# BinaryClock.net
KiCad netlist of a schematic drawn in EAGLE
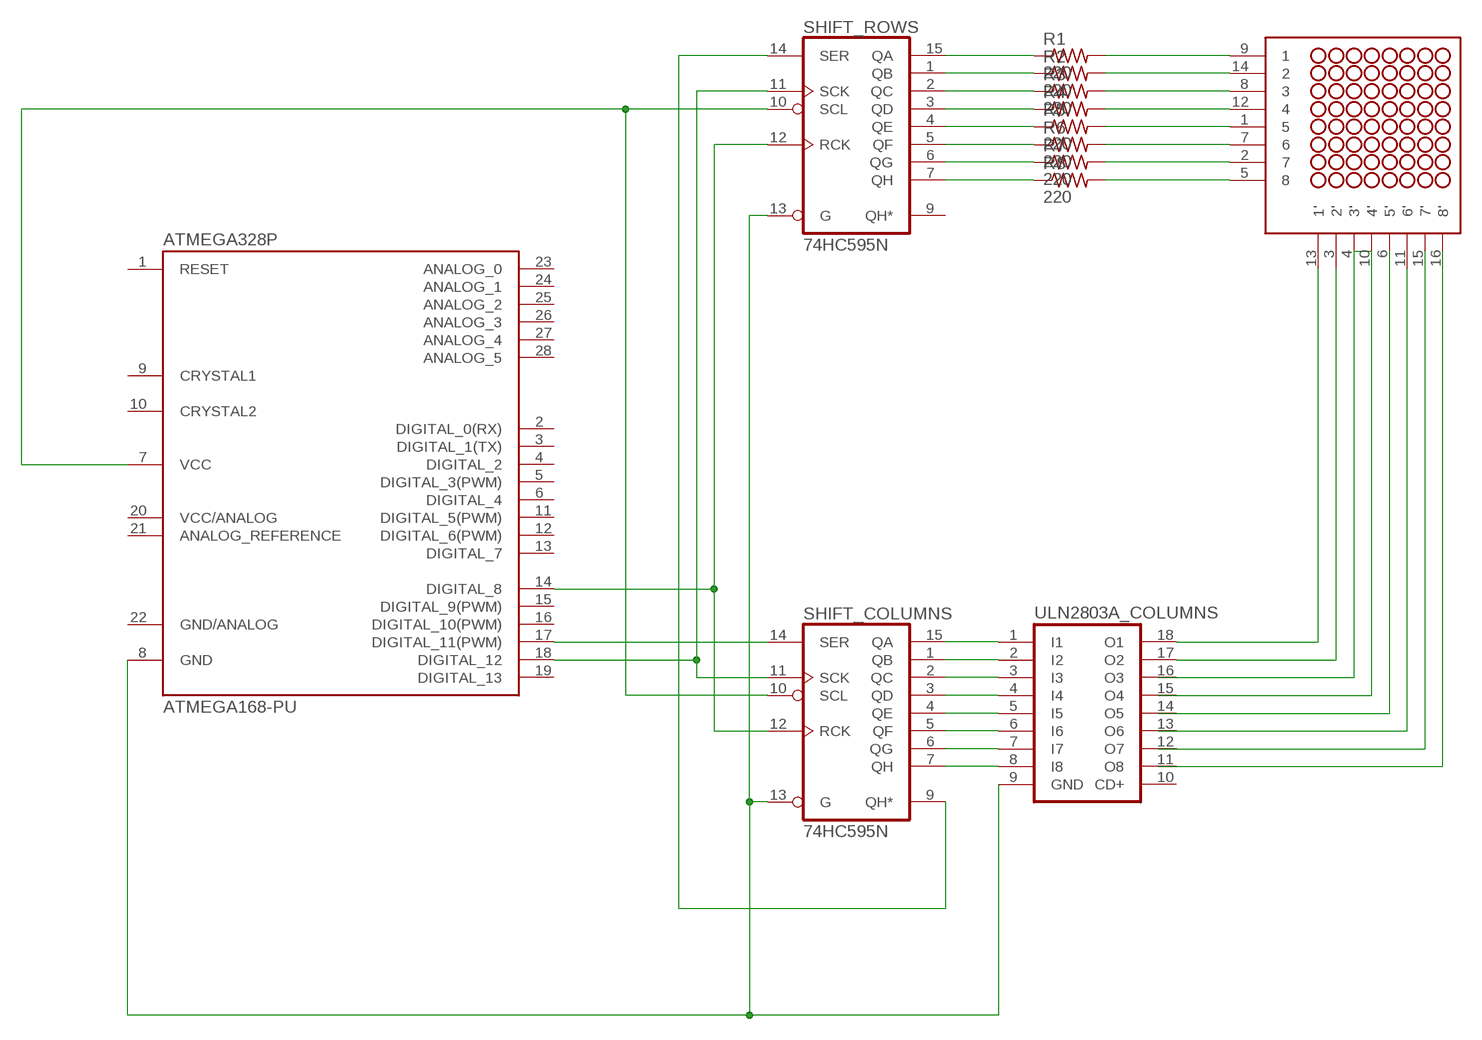
[diagram p0: schematic, sheet 1]

(export (version "E")
  (design (tool "Eeschema 10.0.6"))
  (components
    (comp (ref "ATMEGA328P")
      (value "ATMEGA168-PU")
      (footprint "eagle-import:DIL28-3")
      (libsource (lib "eagle-import") (part "ATMEGA168-PU"))
    )
    (comp (ref "LD1088BS")
      (value "NFM-12881BG-11")
      (footprint "eagle-import:NFM-12881BG-11")
      (libsource (lib "eagle-import") (part "NFM-12881BG-11"))
    )
    (comp (ref "R1")
      (value "220")
      (footprint "eagle-import:0207_10")
      (libsource (lib "eagle-import") (part "R-US_0207/10"))
    )
    (comp (ref "R2")
      (value "220")
      (footprint "eagle-import:0207_10")
      (libsource (lib "eagle-import") (part "R-US_0207/10"))
    )
    (comp (ref "R3")
      (value "220")
      (footprint "eagle-import:0207_10")
      (libsource (lib "eagle-import") (part "R-US_0207/10"))
    )
    (comp (ref "R4")
      (value "R-US_0207/10")
      (footprint "eagle-import:0207_10")
      (libsource (lib "eagle-import") (part "R-US_0207/10"))
    )
    (comp (ref "R5")
      (value "220")
      (footprint "eagle-import:0207_10")
      (libsource (lib "eagle-import") (part "R-US_0207/10"))
    )
    (comp (ref "R6")
      (value "220")
      (footprint "eagle-import:0207_10")
      (libsource (lib "eagle-import") (part "R-US_0207/10"))
    )
    (comp (ref "R7")
      (value "220")
      (footprint "eagle-import:0207_10")
      (libsource (lib "eagle-import") (part "R-US_0207/10"))
    )
    (comp (ref "R8")
      (value "220")
      (footprint "eagle-import:0207_10")
      (libsource (lib "eagle-import") (part "R-US_0207/10"))
    )
    (comp (ref "SHIFT_COLUMNS")
      (value "74HC595N")
      (footprint "eagle-import:DIL16")
      (libsource (lib "eagle-import") (part "74595NHC"))
    )
    (comp (ref "SHIFT_ROWS")
      (value "74HC595N")
      (footprint "eagle-import:DIL16")
      (libsource (lib "eagle-import") (part "74595NHC"))
    )
    (comp (ref "ULN2803A_COLUMNS")
      (value "ULN2803A")
      (footprint "eagle-import:DIL18")
      (libsource (lib "eagle-import") (part "ULN2803A"))
    )
  )
  (nets
    (net (code "1") (name "/GND{slash}ANALOG") (class "Default")
      (node (ref "ATMEGA328P") (pin "22") (pinfunction "GND/ANALOG_22") (pintype "power_in"))
    )
    (net (code "2") (name "Net-(ATMEGA328P-DIGITAL_8)") (class "Default")
      (node (ref "ATMEGA328P") (pin "14") (pinfunction "DIGITAL_8_14") (pintype "bidirectional"))
      (node (ref "SHIFT_COLUMNS") (pin "12") (pinfunction "RCK_12") (pintype "input"))
      (node (ref "SHIFT_ROWS") (pin "12") (pinfunction "RCK_12") (pintype "input"))
    )
    (net (code "3") (name "Net-(ATMEGA328P-DIGITAL_11(PWM))") (class "Default")
      (node (ref "ATMEGA328P") (pin "17") (pinfunction "DIGITAL_11(PWM)_17") (pintype "bidirectional"))
      (node (ref "SHIFT_COLUMNS") (pin "14") (pinfunction "SER_14") (pintype "input"))
    )
    (net (code "4") (name "Net-(ATMEGA328P-DIGITAL_12)") (class "Default")
      (node (ref "ATMEGA328P") (pin "18") (pinfunction "DIGITAL_12_18") (pintype "bidirectional"))
      (node (ref "SHIFT_COLUMNS") (pin "11") (pinfunction "SCK_11") (pintype "input"))
      (node (ref "SHIFT_ROWS") (pin "11") (pinfunction "SCK_11") (pintype "input"))
    )
    (net (code "5") (name "Net-(ATMEGA328P-GND)") (class "Default")
      (node (ref "ATMEGA328P") (pin "8") (pinfunction "GND_8") (pintype "power_in"))
      (node (ref "SHIFT_COLUMNS") (pin "13") (pinfunction "G_13") (pintype "input"))
      (node (ref "SHIFT_ROWS") (pin "13") (pinfunction "G_13") (pintype "input"))
      (node (ref "ULN2803A_COLUMNS") (pin "9") (pinfunction "GND_9") (pintype "power_in"))
    )
    (net (code "6") (name "Net-(ATMEGA328P-VCC)") (class "Default")
      (node (ref "ATMEGA328P") (pin "7") (pinfunction "VCC_7") (pintype "power_in"))
      (node (ref "SHIFT_COLUMNS") (pin "10") (pinfunction "SCL_10") (pintype "input"))
      (node (ref "SHIFT_ROWS") (pin "10") (pinfunction "SCL_10") (pintype "input"))
    )
    (net (code "7") (name "Net-(LD1088BS-1')") (class "Default")
      (node (ref "LD1088BS") (pin "13") (pinfunction "1'_13") (pintype "output"))
      (node (ref "ULN2803A_COLUMNS") (pin "18") (pinfunction "O1_18") (pintype "open_collector"))
    )
    (net (code "8") (name "Net-(LD1088BS-1)") (class "Default")
      (node (ref "LD1088BS") (pin "9") (pinfunction "1_9") (pintype "input"))
      (node (ref "R1") (pin "2") (pinfunction "2_2") (pintype "passive"))
    )
    (net (code "9") (name "Net-(LD1088BS-2')") (class "Default")
      (node (ref "LD1088BS") (pin "3") (pinfunction "2'_3") (pintype "output"))
      (node (ref "ULN2803A_COLUMNS") (pin "17") (pinfunction "O2_17") (pintype "open_collector"))
    )
    (net (code "10") (name "Net-(LD1088BS-2)") (class "Default")
      (node (ref "LD1088BS") (pin "14") (pinfunction "2_14") (pintype "input"))
      (node (ref "R2") (pin "2") (pinfunction "2_2") (pintype "passive"))
    )
    (net (code "11") (name "Net-(LD1088BS-3)") (class "Default")
      (node (ref "LD1088BS") (pin "8") (pinfunction "3_8") (pintype "input"))
      (node (ref "R3") (pin "2") (pinfunction "2_2") (pintype "passive"))
    )
    (net (code "12") (name "Net-(LD1088BS-4)") (class "Default")
      (node (ref "LD1088BS") (pin "12") (pinfunction "4_12") (pintype "input"))
      (node (ref "R4") (pin "2") (pinfunction "2_2") (pintype "passive"))
    )
    (net (code "13") (name "Net-(LD1088BS-5)") (class "Default")
      (node (ref "LD1088BS") (pin "1") (pinfunction "5_1") (pintype "input"))
      (node (ref "R5") (pin "2") (pinfunction "2_2") (pintype "passive"))
    )
    (net (code "14") (name "Net-(LD1088BS-6)") (class "Default")
      (node (ref "LD1088BS") (pin "7") (pinfunction "6_7") (pintype "input"))
      (node (ref "R6") (pin "2") (pinfunction "2_2") (pintype "passive"))
    )
    (net (code "15") (name "Net-(LD1088BS-7)") (class "Default")
      (node (ref "LD1088BS") (pin "2") (pinfunction "7_2") (pintype "input"))
      (node (ref "R7") (pin "2") (pinfunction "2_2") (pintype "passive"))
    )
    (net (code "16") (name "Net-(LD1088BS-8)") (class "Default")
      (node (ref "LD1088BS") (pin "5") (pinfunction "8_5") (pintype "input"))
      (node (ref "R8") (pin "2") (pinfunction "2_2") (pintype "passive"))
    )
    (net (code "17") (name "Net-(SHIFT_COLUMNSA-QA)") (class "Default")
      (node (ref "SHIFT_COLUMNS") (pin "15") (pinfunction "QA_15") (pintype "tri_state"))
      (node (ref "ULN2803A_COLUMNS") (pin "1") (pinfunction "I1_1") (pintype "input"))
    )
    (net (code "18") (name "Net-(SHIFT_COLUMNSA-QB)") (class "Default")
      (node (ref "SHIFT_COLUMNS") (pin "1") (pinfunction "QB_1") (pintype "tri_state"))
      (node (ref "ULN2803A_COLUMNS") (pin "2") (pinfunction "I2_2") (pintype "input"))
    )
    (net (code "19") (name "Net-(SHIFT_COLUMNSA-QC)") (class "Default")
      (node (ref "SHIFT_COLUMNS") (pin "2") (pinfunction "QC_2") (pintype "tri_state"))
      (node (ref "ULN2803A_COLUMNS") (pin "3") (pinfunction "I3_3") (pintype "input"))
    )
    (net (code "20") (name "Net-(SHIFT_COLUMNSA-QD)") (class "Default")
      (node (ref "SHIFT_COLUMNS") (pin "3") (pinfunction "QD_3") (pintype "tri_state"))
      (node (ref "ULN2803A_COLUMNS") (pin "4") (pinfunction "I4_4") (pintype "input"))
    )
    (net (code "21") (name "Net-(SHIFT_COLUMNSA-QE)") (class "Default")
      (node (ref "SHIFT_COLUMNS") (pin "4") (pinfunction "QE_4") (pintype "tri_state"))
      (node (ref "ULN2803A_COLUMNS") (pin "5") (pinfunction "I5_5") (pintype "input"))
    )
    (net (code "22") (name "Net-(SHIFT_COLUMNSA-QF)") (class "Default")
      (node (ref "SHIFT_COLUMNS") (pin "5") (pinfunction "QF_5") (pintype "tri_state"))
      (node (ref "ULN2803A_COLUMNS") (pin "6") (pinfunction "I6_6") (pintype "input"))
    )
    (net (code "23") (name "Net-(SHIFT_COLUMNSA-QG)") (class "Default")
      (node (ref "SHIFT_COLUMNS") (pin "6") (pinfunction "QG_6") (pintype "tri_state"))
      (node (ref "ULN2803A_COLUMNS") (pin "7") (pinfunction "I7_7") (pintype "input"))
    )
    (net (code "24") (name "Net-(SHIFT_COLUMNSA-QH)") (class "Default")
      (node (ref "SHIFT_COLUMNS") (pin "7") (pinfunction "QH_7") (pintype "tri_state"))
      (node (ref "ULN2803A_COLUMNS") (pin "8") (pinfunction "I8_8") (pintype "input"))
    )
    (net (code "25") (name "Net-(SHIFT_COLUMNSA-QH*)") (class "Default")
      (node (ref "SHIFT_COLUMNS") (pin "9") (pinfunction "QH*_9") (pintype "tri_state"))
      (node (ref "SHIFT_ROWS") (pin "14") (pinfunction "SER_14") (pintype "input"))
    )
    (net (code "26") (name "Net-(SHIFT_ROWSA-QA)") (class "Default")
      (node (ref "R1") (pin "1") (pinfunction "1_1") (pintype "passive"))
      (node (ref "SHIFT_ROWS") (pin "15") (pinfunction "QA_15") (pintype "tri_state"))
    )
    (net (code "27") (name "Net-(SHIFT_ROWSA-QB)") (class "Default")
      (node (ref "R2") (pin "1") (pinfunction "1_1") (pintype "passive"))
      (node (ref "SHIFT_ROWS") (pin "1") (pinfunction "QB_1") (pintype "tri_state"))
    )
    (net (code "28") (name "Net-(SHIFT_ROWSA-QC)") (class "Default")
      (node (ref "R3") (pin "1") (pinfunction "1_1") (pintype "passive"))
      (node (ref "SHIFT_ROWS") (pin "2") (pinfunction "QC_2") (pintype "tri_state"))
    )
    (net (code "29") (name "Net-(SHIFT_ROWSA-QD)") (class "Default")
      (node (ref "R4") (pin "1") (pinfunction "1_1") (pintype "passive"))
      (node (ref "SHIFT_ROWS") (pin "3") (pinfunction "QD_3") (pintype "tri_state"))
    )
    (net (code "30") (name "Net-(SHIFT_ROWSA-QE)") (class "Default")
      (node (ref "R5") (pin "1") (pinfunction "1_1") (pintype "passive"))
      (node (ref "SHIFT_ROWS") (pin "4") (pinfunction "QE_4") (pintype "tri_state"))
    )
    (net (code "31") (name "Net-(SHIFT_ROWSA-QF)") (class "Default")
      (node (ref "R6") (pin "1") (pinfunction "1_1") (pintype "passive"))
      (node (ref "SHIFT_ROWS") (pin "5") (pinfunction "QF_5") (pintype "tri_state"))
    )
    (net (code "32") (name "Net-(SHIFT_ROWSA-QG)") (class "Default")
      (node (ref "R7") (pin "1") (pinfunction "1_1") (pintype "passive"))
      (node (ref "SHIFT_ROWS") (pin "6") (pinfunction "QG_6") (pintype "tri_state"))
    )
    (net (code "33") (name "Net-(SHIFT_ROWSA-QH)") (class "Default")
      (node (ref "R8") (pin "1") (pinfunction "1_1") (pintype "passive"))
      (node (ref "SHIFT_ROWS") (pin "7") (pinfunction "QH_7") (pintype "tri_state"))
    )
    (net (code "34") (name "unconnected-(ATMEGA328P-ANALOG_0-Pad23)") (class "Default")
      (node (ref "ATMEGA328P") (pin "23") (pinfunction "ANALOG_0_23") (pintype "bidirectional"))
    )
    (net (code "35") (name "unconnected-(ATMEGA328P-ANALOG_1-Pad24)") (class "Default")
      (node (ref "ATMEGA328P") (pin "24") (pinfunction "ANALOG_1_24") (pintype "bidirectional"))
    )
    (net (code "36") (name "unconnected-(ATMEGA328P-ANALOG_2-Pad25)") (class "Default")
      (node (ref "ATMEGA328P") (pin "25") (pinfunction "ANALOG_2_25") (pintype "bidirectional"))
    )
    (net (code "37") (name "unconnected-(ATMEGA328P-ANALOG_3-Pad26)") (class "Default")
      (node (ref "ATMEGA328P") (pin "26") (pinfunction "ANALOG_3_26") (pintype "bidirectional"))
    )
    (net (code "38") (name "unconnected-(ATMEGA328P-ANALOG_4-Pad27)") (class "Default")
      (node (ref "ATMEGA328P") (pin "27") (pinfunction "ANALOG_4_27") (pintype "bidirectional"))
    )
    (net (code "39") (name "unconnected-(ATMEGA328P-ANALOG_5-Pad28)") (class "Default")
      (node (ref "ATMEGA328P") (pin "28") (pinfunction "ANALOG_5_28") (pintype "bidirectional"))
    )
    (net (code "40") (name "unconnected-(ATMEGA328P-ANALOG_REFERENCE-Pad21)") (class "Default")
      (node (ref "ATMEGA328P") (pin "21") (pinfunction "ANALOG_REFERENCE_21") (pintype "passive"))
    )
    (net (code "41") (name "unconnected-(ATMEGA328P-CRYSTAL1-Pad9)") (class "Default")
      (node (ref "ATMEGA328P") (pin "9") (pinfunction "CRYSTAL1_9") (pintype "bidirectional"))
    )
    (net (code "42") (name "unconnected-(ATMEGA328P-CRYSTAL2-Pad10)") (class "Default")
      (node (ref "ATMEGA328P") (pin "10") (pinfunction "CRYSTAL2_10") (pintype "bidirectional"))
    )
    (net (code "43") (name "unconnected-(ATMEGA328P-DIGITAL_0(RX)-Pad2)") (class "Default")
      (node (ref "ATMEGA328P") (pin "2") (pinfunction "DIGITAL_0(RX)_2") (pintype "bidirectional"))
    )
    (net (code "44") (name "unconnected-(ATMEGA328P-DIGITAL_1(TX)-Pad3)") (class "Default")
      (node (ref "ATMEGA328P") (pin "3") (pinfunction "DIGITAL_1(TX)_3") (pintype "bidirectional"))
    )
    (net (code "45") (name "unconnected-(ATMEGA328P-DIGITAL_2-Pad4)") (class "Default")
      (node (ref "ATMEGA328P") (pin "4") (pinfunction "DIGITAL_2_4") (pintype "bidirectional"))
    )
    (net (code "46") (name "unconnected-(ATMEGA328P-DIGITAL_3(PWM)-Pad5)") (class "Default")
      (node (ref "ATMEGA328P") (pin "5") (pinfunction "DIGITAL_3(PWM)_5") (pintype "bidirectional"))
    )
    (net (code "47") (name "unconnected-(ATMEGA328P-DIGITAL_4-Pad6)") (class "Default")
      (node (ref "ATMEGA328P") (pin "6") (pinfunction "DIGITAL_4_6") (pintype "bidirectional"))
    )
    (net (code "48") (name "unconnected-(ATMEGA328P-DIGITAL_5(PWM)-Pad11)") (class "Default")
      (node (ref "ATMEGA328P") (pin "11") (pinfunction "DIGITAL_5(PWM)_11") (pintype "bidirectional"))
    )
    (net (code "49") (name "unconnected-(ATMEGA328P-DIGITAL_6(PWM)-Pad12)") (class "Default")
      (node (ref "ATMEGA328P") (pin "12") (pinfunction "DIGITAL_6(PWM)_12") (pintype "bidirectional"))
    )
    (net (code "50") (name "unconnected-(ATMEGA328P-DIGITAL_7-Pad13)") (class "Default")
      (node (ref "ATMEGA328P") (pin "13") (pinfunction "DIGITAL_7_13") (pintype "bidirectional"))
    )
    (net (code "51") (name "unconnected-(ATMEGA328P-DIGITAL_9(PWM)-Pad15)") (class "Default")
      (node (ref "ATMEGA328P") (pin "15") (pinfunction "DIGITAL_9(PWM)_15") (pintype "bidirectional"))
    )
    (net (code "52") (name "unconnected-(ATMEGA328P-DIGITAL_10(PWM)-Pad16)") (class "Default")
      (node (ref "ATMEGA328P") (pin "16") (pinfunction "DIGITAL_10(PWM)_16") (pintype "bidirectional"))
    )
    (net (code "53") (name "unconnected-(ATMEGA328P-DIGITAL_13-Pad19)") (class "Default")
      (node (ref "ATMEGA328P") (pin "19") (pinfunction "DIGITAL_13_19") (pintype "bidirectional"))
    )
    (net (code "54") (name "unconnected-(ATMEGA328P-RESET-Pad1)") (class "Default")
      (node (ref "ATMEGA328P") (pin "1") (pinfunction "RESET_1") (pintype "bidirectional"))
    )
    (net (code "55") (name "unconnected-(ATMEGA328P-VCC{slash}ANALOG-Pad20)") (class "Default")
      (node (ref "ATMEGA328P") (pin "20") (pinfunction "VCC/ANALOG_20") (pintype "passive"))
    )
    (net (code "56") (name "unconnected-(LD1088BS-3'-Pad4)") (class "Default")
      (node (ref "LD1088BS") (pin "4") (pinfunction "3'_4") (pintype "output"))
    )
    (net (code "57") (name "unconnected-(LD1088BS-4'-Pad10)") (class "Default")
      (node (ref "LD1088BS") (pin "10") (pinfunction "4'_10") (pintype "output"))
    )
    (net (code "58") (name "unconnected-(LD1088BS-5'-Pad6)") (class "Default")
      (node (ref "LD1088BS") (pin "6") (pinfunction "5'_6") (pintype "output"))
    )
    (net (code "59") (name "unconnected-(LD1088BS-6'-Pad11)") (class "Default")
      (node (ref "LD1088BS") (pin "11") (pinfunction "6'_11") (pintype "output"))
    )
    (net (code "60") (name "unconnected-(LD1088BS-7'-Pad15)") (class "Default")
      (node (ref "LD1088BS") (pin "15") (pinfunction "7'_15") (pintype "output"))
    )
    (net (code "61") (name "unconnected-(LD1088BS-8'-Pad16)") (class "Default")
      (node (ref "LD1088BS") (pin "16") (pinfunction "8'_16") (pintype "output"))
    )
    (net (code "62") (name "unconnected-(SHIFT_ROWSA-QH*-Pad9)") (class "Default")
      (node (ref "SHIFT_ROWS") (pin "9") (pinfunction "QH*_9") (pintype "tri_state"))
    )
    (net (code "63") (name "unconnected-(ULN2803A_COLUMNS-CD+-Pad10)") (class "Default")
      (node (ref "ULN2803A_COLUMNS") (pin "10") (pinfunction "CD+_10") (pintype "passive"))
    )
    (net (code "64") (name "unconnected-(ULN2803A_COLUMNS-O3-Pad16)") (class "Default")
      (node (ref "ULN2803A_COLUMNS") (pin "16") (pinfunction "O3_16") (pintype "open_collector"))
    )
    (net (code "65") (name "unconnected-(ULN2803A_COLUMNS-O4-Pad15)") (class "Default")
      (node (ref "ULN2803A_COLUMNS") (pin "15") (pinfunction "O4_15") (pintype "open_collector"))
    )
    (net (code "66") (name "unconnected-(ULN2803A_COLUMNS-O5-Pad14)") (class "Default")
      (node (ref "ULN2803A_COLUMNS") (pin "14") (pinfunction "O5_14") (pintype "open_collector"))
    )
    (net (code "67") (name "unconnected-(ULN2803A_COLUMNS-O6-Pad13)") (class "Default")
      (node (ref "ULN2803A_COLUMNS") (pin "13") (pinfunction "O6_13") (pintype "open_collector"))
    )
    (net (code "68") (name "unconnected-(ULN2803A_COLUMNS-O7-Pad12)") (class "Default")
      (node (ref "ULN2803A_COLUMNS") (pin "12") (pinfunction "O7_12") (pintype "open_collector"))
    )
    (net (code "69") (name "unconnected-(ULN2803A_COLUMNS-O8-Pad11)") (class "Default")
      (node (ref "ULN2803A_COLUMNS") (pin "11") (pinfunction "O8_11") (pintype "open_collector"))
    )
  )
)
